# JacdacRgbLed1Ec30_77.net
KiCad netlist of a schematic drawn in Altium Designer
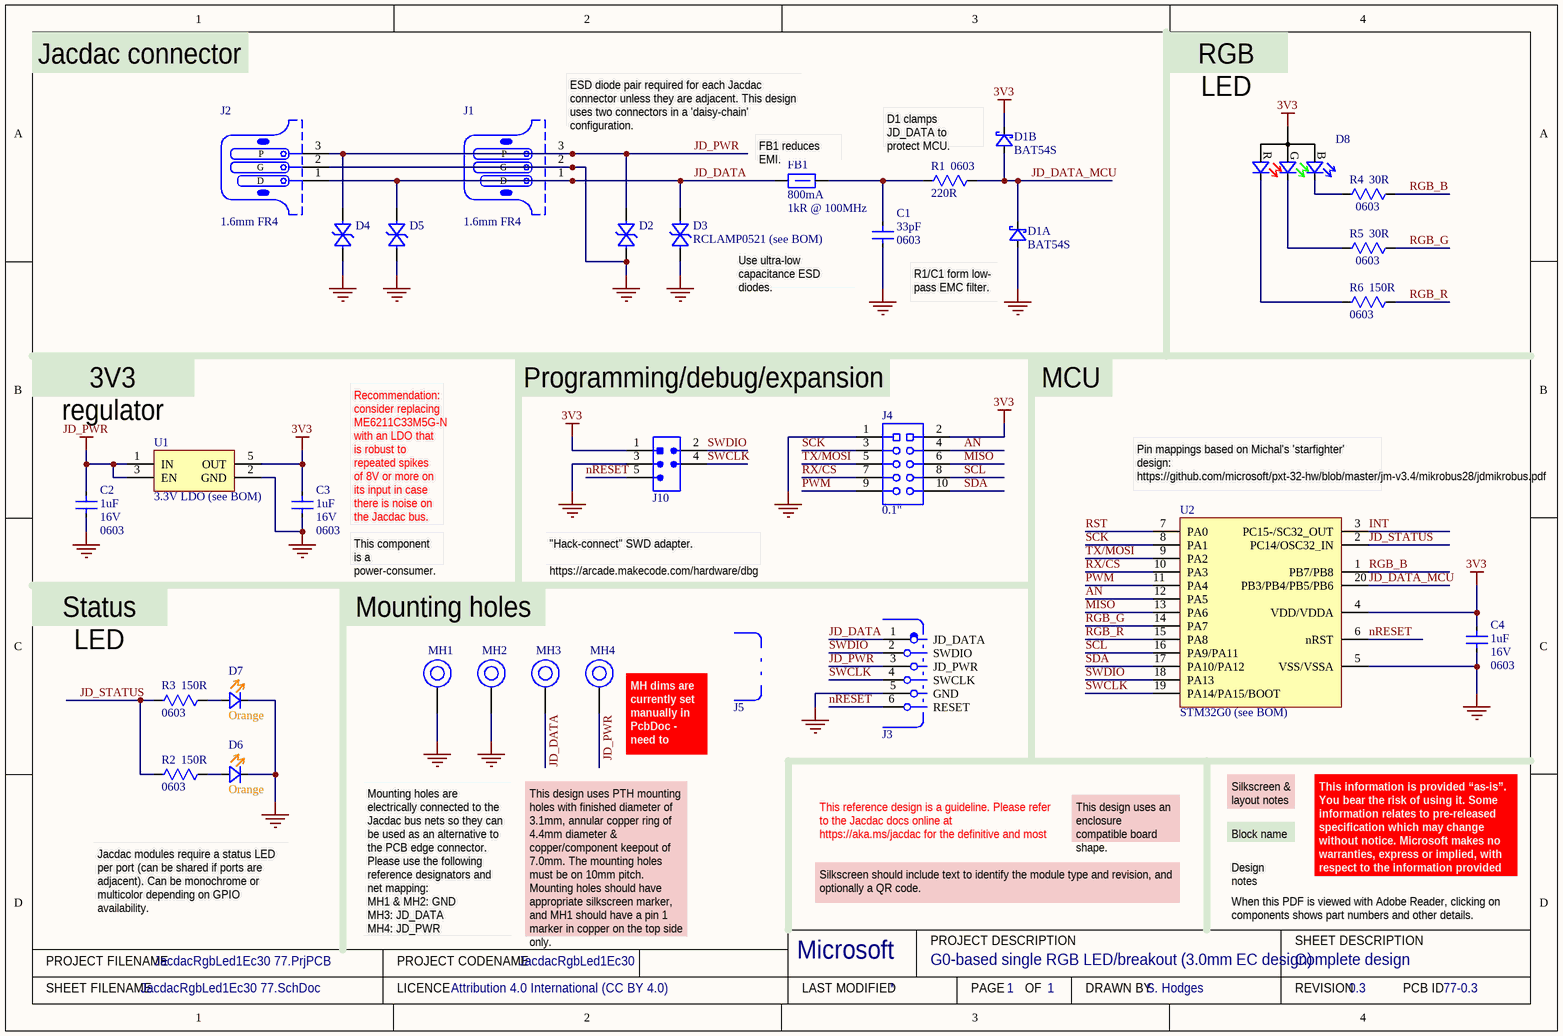
[diagram p0: JacdacRgbLed1Ec30 77.SchDoc]

(export (version "E")
  (design (tool "Eeschema 10.0.6"))
  (components
    (comp (ref "C1")
      (value "33pF")
      (footprint "CC0603")
      (description "Cap 33PF 50V 0603 SMD 5% NP0")
      (fields
        (field (name "VOLTAGE") "50V")
        (field (name "CAPACITANCE") "33pF")
        (field (name "TOLERANCE") "5%")
        (field (name "CASE/PACKAGE") "0603")
      )
      (libsource (lib "Yageo") (part "CC0603JRNPO9BN330"))
    )
    (comp (ref "C2")
      (value "1uF 16V")
      (footprint "SAMSUNG-CAP-0603:C0603 - without outline")
      (description "SMD Multilayer Ceramic Capacitor, 1 µF, 16 V, 0603 [1608 Metric], ± 10%, X5R, CL Series")
      (fields
        (field (name "TOLERANCE") "10%")
        (field (name "VOLTAGE") "16V")
        (field (name "CASE/PACKAGE") "0603")
        (field (name "CAPACITANCE") "1uF")
      )
      (libsource (lib "Samsung") (part "CL10A105KO8NNNC"))
    )
    (comp (ref "C3")
      (value "1uF 16V")
      (footprint "SAMSUNG-CAP-0603:C0603 - without outline")
      (description "SMD Multilayer Ceramic Capacitor, 1 µF, 16 V, 0603 [1608 Metric], ± 10%, X5R, CL Series")
      (fields
        (field (name "TOLERANCE") "10%")
        (field (name "VOLTAGE") "16V")
        (field (name "CASE/PACKAGE") "0603")
        (field (name "CAPACITANCE") "1uF")
      )
      (libsource (lib "Samsung") (part "CL10A105KO8NNNC"))
    )
    (comp (ref "C4")
      (value "1uF 16V")
      (footprint "SAMSUNG-CAP-0603:C0603 - without outline")
      (description "SMD Multilayer Ceramic Capacitor, 1 µF, 16 V, 0603 [1608 Metric], ± 10%, X5R, CL Series")
      (fields
        (field (name "TOLERANCE") "10%")
        (field (name "VOLTAGE") "16V")
        (field (name "CASE/PACKAGE") "0603")
        (field (name "CAPACITANCE") "1uF")
      )
      (libsource (lib "Samsung") (part "CL10A105KO8NNNC"))
    )
    (comp (ref "D1")
      (value "BAT54S")
      (footprint "NXP-BAT54S-TO-236AB - without outline")
      (description "DIODE ARRAY SCHOTTKY 30V SOT23")
      (fields (field (name "MANUFACTURER") "Nexperia") (field (name "MANUFACTURER PART NUMBER") "BAT54S"))
      (libsource (lib "NXP") (part "BAT54S"))
    )
    (comp (ref "D2")
      (value "RCLAMP0521P-N")
      (footprint "TVS 0402 - L")
      (description "Bidirectional 5V (Max) 6V 16V 3.5A (8/20us) 0402 TVS RoHS")
      (fields (field (name "CREATED BY") "D Gakure") (field (name "CHECKED BY") "?"))
      (libsource (lib "BornSemiconductor") (part "RCLAMP0521P-N"))
    )
    (comp (ref "D3")
      (value "RCLAMP0521P-N")
      (footprint "TVS 0402 - L")
      (description "Bidirectional 5V (Max) 6V 16V 3.5A (8/20us) 0402 TVS RoHS")
      (fields
        (field (name "MANUFACTURER PART NUMBER 1") "RCLAMP0521 (see BOM)")
        (field (name "CREATED BY") "D Gakure")
        (field (name "CHECKED BY") "?")
      )
      (libsource (lib "BornSemiconductor") (part "RCLAMP0521P-N"))
    )
    (comp (ref "D4")
      (value "RCLAMP0521P-N")
      (footprint "TVS 0402 - L")
      (description "Bidirectional 5V (Max) 6V 16V 3.5A (8/20us) 0402 TVS RoHS")
      (fields (field (name "CREATED BY") "D Gakure") (field (name "CHECKED BY") "?"))
      (libsource (lib "BornSemiconductor") (part "RCLAMP0521P-N"))
    )
    (comp (ref "D5")
      (value "RCLAMP0521P-N")
      (footprint "TVS 0402 - L")
      (description "Bidirectional 5V (Max) 6V 16V 3.5A (8/20us) 0402 TVS RoHS")
      (fields (field (name "CREATED BY") "D Gakure") (field (name "CHECKED BY") "?"))
      (libsource (lib "BornSemiconductor") (part "RCLAMP0521P-N"))
    )
    (comp (ref "D6")
      (value "~")
      (footprint "0603 Orange")
      (description "LED ORANGE DIFFUSED 0603 SMD")
      (fields (field (name "COLOUR") "Orange"))
      (libsource (lib "EverlightElec") (part "19-217/S2C-AQ1R1B/3T"))
    )
    (comp (ref "D7")
      (value "~")
      (footprint "0603 Orange")
      (description "LED ORANGE DIFFUSED 0603 SMD")
      (fields (field (name "COLOUR") "Orange"))
      (libsource (lib "EverlightElec") (part "19-217/S2C-AQ1R1B/3T"))
    )
    (comp (ref "D8")
      (value "TZ-P4-1615RGBTCA1-0.55T")
      (footprint "TZ-P4-1615RGBTCA1-0.55T")
      (description "1615 Light Emitting Diodes (LED) RoHS")
      (fields (field (name "CREATED BY") "D. Gakure") (field (name "CHECKED BY") "?"))
      (libsource (lib "Tuozhan") (part "TZ-P4-1615RGBTCA1-0.55T"))
    )
    (comp (ref "FB1")
      (value "TDK MPZ1608S102ATA00")
      (footprint "TDK MPZ1608 0.8mm - without outline")
      (description "0603 1k@100MHz 0.8A chip")
      (fields
        (field (name "TOLERANCE") "25%")
        (field (name "MANUFACTURER") "TDK")
        (field (name "CURRENT RATING") "800mA")
        (field (name "IMPEDANCE") "1kR @ 100MHz")
      )
      (libsource (lib "TDK") (part "TDK MPZ1608S102ATA00"))
    )
    (comp (ref "J1")
      (value "3 pin JACDAC edge connector")
      (footprint "JACDAC_EDGE_CONNECTOR_NO_TRACES")
      (description "3 pin Jacdac edge connector 1.27mm pitch")
      (fields
        (field (name "MANUFACTURER PART NUMBER") "JACDAC_EDGE_CONNECTOR")
        (field (name "PCB TYPE") "1.6mm FR4")
        (field (name "CHECKED BY") "?")
        (field (name "CREATED BY") "D. Gakure")
      )
      (libsource (lib "generic-con") (part "Jacdac edge connector"))
    )
    (comp (ref "J2")
      (value "3 pin JACDAC edge connector")
      (footprint "JACDAC_edge_connector:JACDAC_EDGE_CONNECTOR_NO_TRACES")
      (description "3 pin Jacdac edge connector 1.27mm pitch")
      (fields
        (field (name "MANUFACTURER PART NUMBER") "JACDAC_EDGE_CONNECTOR")
        (field (name "PCB TYPE") "1.6mm FR4")
        (field (name "CHECKED BY") "?")
        (field (name "CREATED BY") "D. Gakure")
      )
      (libsource (lib "generic-con") (part "Jacdac edge connector"))
    )
    (comp (ref "J3")
      (value "3x2 way 'mouse bite' connector for Jacdac and SWD")
      (footprint "MiscConnectors:MOUSEBITE_CONNECTOR_3x2")
      (libsource (lib "generic-con") (part "MOUSEBITE_CONNECTOR_3x2_JDSWD"))
    )
    (comp (ref "J4")
      (value "0.1\"")
      (footprint "generic-con-0.1inch:Generic 2x5 2.54mm header")
      (description "2.54mm, 5x2 way, vertical, square pin, gold plate")
      (fields (field (name "MANUFACTURER") "Multicomp") (field (name "MANUFACTURER PART NUMBER") "2213S-10G"))
      (libsource (lib "generic-con") (part "Header Multicomp 2213S-10G-whitesch"))
    )
    (comp (ref "J5")
      (value "3 way 'mouse bite' connector")
      (footprint "MiscConnectors:MOUSEBITE_NOCONNECTOR_3")
      (libsource (lib "generic-con") (part "MOUSEBITE_NOCONNECTOR_3"))
    )
    (comp (ref "J10")
      (value "Hack Connect Mini 1.27 mm pitch 2-row")
      (footprint "HACK_CONNECT_MINI_5_X_1_27")
      (libsource (lib "HackConnect") (part "HACK_CONNECT_MINI"))
    )
    (comp (ref "MH1")
      (value "MH_6.5MMK_4.5MMC_3.0MMD_PTH")
      (footprint "MH_6.5MMK_4.5MMC_3.0MMD_PTH")
      (description "Mounting Hole 6.5mm keepout, 4.5mm annualar ring and 3.0mm Drill PTH")
      (libsource (lib "generic") (part "MH_6.5MMK_4.5MMC_3.0MMD_PTH"))
    )
    (comp (ref "MH2")
      (value "MH_6.5MMK_4.5MMC_3.0MMD_PTH")
      (footprint "MH_6.5MMK_4.5MMC_3.0MMD_PTH")
      (description "Mounting Hole 6.5mm keepout, 4.5mm annualar ring and 3.0mm Drill PTH")
      (libsource (lib "generic") (part "MH_6.5MMK_4.5MMC_3.0MMD_PTH"))
    )
    (comp (ref "MH3")
      (value "MH_6.5MMK_4.5MMC_3.0MMD_PTH")
      (footprint "MH_6.5MMK_4.5MMC_3.0MMD_PTH")
      (description "Mounting Hole 6.5mm keepout, 4.5mm annualar ring and 3.0mm Drill PTH")
      (libsource (lib "generic") (part "MH_6.5MMK_4.5MMC_3.0MMD_PTH"))
    )
    (comp (ref "MH4")
      (value "MH_6.5MMK_4.5MMC_3.0MMD_PTH")
      (footprint "MH_6.5MMK_4.5MMC_3.0MMD_PTH")
      (description "Mounting Hole 6.5mm keepout, 4.5mm annualar ring and 3.0mm Drill PTH")
      (libsource (lib "generic") (part "MH_6.5MMK_4.5MMC_3.0MMD_PTH"))
    )
    (comp (ref "R1")
      (value "220R")
      (footprint "YAGEO-0603:RC0603")
      (description "Res Thick Film 0603 220 Ohm 1% 0.1W(1/10W) ±100ppm/°C Pad SMD T/R")
      (fields
        (field (name "TOLERANCE") "1%")
        (field (name "RESISTANCE") "220R")
        (field (name "CASE/PACKAGE") "0603")
      )
      (libsource (lib "Yageo") (part "RC0603FR-07220RL"))
    )
    (comp (ref "R2")
      (value "150R")
      (footprint "YAGEO-0603:RC0603")
      (description "Res General Purpose Thick Film 0603 150 Ohm 1% 1/10W ±100ppm/°C Molded SMD Paper T/R")
      (fields
        (field (name "TOLERANCE") "1%")
        (field (name "CASE/PACKAGE") "0603")
        (field (name "RESISTANCE") "150R")
      )
      (libsource (lib "Yageo") (part "RC0603FR-07150RL"))
    )
    (comp (ref "R3")
      (value "150R")
      (footprint "YAGEO-0603:RC0603")
      (description "Res General Purpose Thick Film 0603 150 Ohm 1% 1/10W ±100ppm/°C Molded SMD Paper T/R")
      (fields
        (field (name "TOLERANCE") "1%")
        (field (name "CASE/PACKAGE") "0603")
        (field (name "RESISTANCE") "150R")
      )
      (libsource (lib "Yageo") (part "RC0603FR-07150RL"))
    )
    (comp (ref "R4")
      (value "30R")
      (footprint "YAGEO-0603:RC0603")
      (description "Res Thick Film 0603 30 Ohm 1% 0.1W(1/10W) ±100ppm/C Pad SMD T/R")
      (fields
        (field (name "TOLERANCE") "1%")
        (field (name "RESISTANCE") "30R")
        (field (name "CASE/PACKAGE") "0603")
      )
      (libsource (lib "Yageo") (part "RC0603FR-0730RL"))
    )
    (comp (ref "R5")
      (value "30R")
      (footprint "YAGEO-0603:RC0603")
      (description "Res Thick Film 0603 30 Ohm 1% 0.1W(1/10W) ±100ppm/C Pad SMD T/R")
      (fields
        (field (name "TOLERANCE") "1%")
        (field (name "RESISTANCE") "30R")
        (field (name "CASE/PACKAGE") "0603")
      )
      (libsource (lib "Yageo") (part "RC0603FR-0730RL"))
    )
    (comp (ref "R6")
      (value "150R")
      (footprint "YAGEO-0603:RC0603")
      (description "Res General Purpose Thick Film 0603 150 Ohm 1% 1/10W ±100ppm/°C Molded SMD Paper T/R")
      (fields
        (field (name "TOLERANCE") "1%")
        (field (name "CASE/PACKAGE") "0603")
        (field (name "RESISTANCE") "150R")
      )
      (libsource (lib "Yageo") (part "RC0603FR-07150RL"))
    )
    (comp (ref "U1")
      (value "~")
      (footprint "MICRONE-SOT23-5")
      (description "6V 260mV @ 200mA(typ) - - Fixed 3.3V SOT-23-5 Linear Voltage Regulators (LDO) ROHS")
      (fields
        (field (name "MANUFACTURER PART NUMBER 1") "3.3V LDO (see BOM)")
        (field (name "CREATED") "DG")
        (field (name "CHECKED") "?")
      )
      (libsource (lib "MICRONE(NanjingMicroOneElec)") (part "ME6211C33M5G-N"))
    )
    (comp (ref "U2")
      (value "STM32G0 (see BOM)")
      (footprint "20-TSSOP")
      (description "MCU 32-Bit STM32G031 ARM Cortex-M0+ RISC 32KB Flash 1.7V to 3.6V 20-Pin TSSOP Tube")
      (fields
        (field (name "MANUFACTURER") "STMicroelectronics")
        (field (name "MANUFACTURER PART NUMBER") "STM32G0 (see BOM)")
        (field (name "CREATED BY") "D. Gakure")
        (field (name "CHECKED BY") "?")
      )
      (libsource (lib "ST") (part "STM32G031F6P6"))
    )
  )
  (nets
    (net (code "1") (name "/AN") (class "Default")
      (node (ref "J4") (pin "4") (pinfunction "4_4") (pintype "passive"))
      (node (ref "U2") (pin "12") (pinfunction "PA5_12") (pintype "passive"))
    )
    (net (code "2") (name "/INT") (class "Default")
      (node (ref "U2") (pin "3") (pinfunction "PC15-/SC32_OUT_3") (pintype "passive"))
    )
    (net (code "3") (name "/JD_DATA") (class "Default")
      (node (ref "D3") (pin "1") (pinfunction "K_1") (pintype "passive"))
      (node (ref "D5") (pin "1") (pinfunction "K_1") (pintype "passive"))
      (node (ref "FB1") (pin "1") (pinfunction "1_1") (pintype "passive"))
      (node (ref "J1") (pin "1") (pinfunction "D_1") (pintype "passive"))
      (node (ref "J2") (pin "1") (pinfunction "D_1") (pintype "passive"))
      (node (ref "J3") (pin "1") (pinfunction "JD_DATA_1") (pintype "passive"))
      (node (ref "MH3") (pin "1") (pinfunction "1_1") (pintype "passive"))
    )
    (net (code "4") (name "/JD_DATA_MCU") (class "Default")
      (node (ref "D1") (pin "3") (pinfunction "K_3") (pintype "passive"))
      (node (ref "R1") (pin "2") (pinfunction "2_2") (pintype "passive"))
      (node (ref "U2") (pin "20") (pinfunction "PB3/PB4/PB5/PB6_20") (pintype "power_in"))
    )
    (net (code "5") (name "/JD_STATUS") (class "Default")
      (node (ref "R2") (pin "1") (pinfunction "1_1") (pintype "passive"))
      (node (ref "R3") (pin "1") (pinfunction "1_1") (pintype "passive"))
      (node (ref "U2") (pin "2") (pinfunction "PC14/OSC32_IN_2") (pintype "passive"))
    )
    (net (code "6") (name "/MISO") (class "Default")
      (node (ref "J4") (pin "6") (pinfunction "6_6") (pintype "passive"))
      (node (ref "U2") (pin "13") (pinfunction "PA6_13") (pintype "passive"))
    )
    (net (code "7") (name "/PWM") (class "Default")
      (node (ref "J4") (pin "9") (pinfunction "9_9") (pintype "passive"))
      (node (ref "U2") (pin "11") (pinfunction "PA4_11") (pintype "passive"))
    )
    (net (code "8") (name "/RGB_B") (class "Default")
      (node (ref "R4") (pin "2") (pinfunction "2_2") (pintype "passive"))
      (node (ref "U2") (pin "1") (pinfunction "PB7/PB8_1") (pintype "passive"))
    )
    (net (code "9") (name "/RGB_G") (class "Default")
      (node (ref "R5") (pin "2") (pinfunction "2_2") (pintype "passive"))
      (node (ref "U2") (pin "14") (pinfunction "PA7_14") (pintype "passive"))
    )
    (net (code "10") (name "/RGB_R") (class "Default")
      (node (ref "R6") (pin "2") (pinfunction "2_2") (pintype "passive"))
      (node (ref "U2") (pin "15") (pinfunction "PA8_15") (pintype "passive"))
    )
    (net (code "11") (name "/RST") (class "Default")
      (node (ref "U2") (pin "7") (pinfunction "PA0_7") (pintype "passive"))
    )
    (net (code "12") (name "/RX{slash}CS") (class "Default")
      (node (ref "J4") (pin "7") (pinfunction "7_7") (pintype "passive"))
      (node (ref "U2") (pin "10") (pinfunction "PA3_10") (pintype "passive"))
    )
    (net (code "13") (name "/SCK") (class "Default")
      (node (ref "J4") (pin "3") (pinfunction "3_3") (pintype "passive"))
      (node (ref "U2") (pin "8") (pinfunction "PA1_8") (pintype "passive"))
    )
    (net (code "14") (name "/SCL") (class "Default")
      (node (ref "J4") (pin "8") (pinfunction "8_8") (pintype "passive"))
      (node (ref "U2") (pin "16") (pinfunction "PA9/PA11_16") (pintype "passive"))
    )
    (net (code "15") (name "/SDA") (class "Default")
      (node (ref "J4") (pin "10") (pinfunction "10_10") (pintype "passive"))
      (node (ref "U2") (pin "17") (pinfunction "PA10/PA12_17") (pintype "passive"))
    )
    (net (code "16") (name "/SWCLK") (class "Default")
      (node (ref "J10") (pin "4") (pinfunction "SWCLK_4") (pintype "passive"))
      (node (ref "J3") (pin "4") (pinfunction "SWCLK_4") (pintype "passive"))
      (node (ref "U2") (pin "19") (pinfunction "PA14/PA15/BOOT_19") (pintype "passive"))
    )
    (net (code "17") (name "/SWDIO") (class "Default")
      (node (ref "J10") (pin "2") (pinfunction "SWDIO_2") (pintype "passive"))
      (node (ref "J3") (pin "2") (pinfunction "SWDIO_2") (pintype "passive"))
      (node (ref "U2") (pin "18") (pinfunction "PA13_18") (pintype "passive"))
    )
    (net (code "18") (name "/TX{slash}MOSI") (class "Default")
      (node (ref "J4") (pin "5") (pinfunction "5_5") (pintype "passive"))
      (node (ref "U2") (pin "9") (pinfunction "PA2_9") (pintype "passive"))
    )
    (net (code "19") (name "/nRESET") (class "Default")
      (node (ref "J10") (pin "5") (pinfunction "RESET_5") (pintype "passive"))
      (node (ref "J3") (pin "6") (pinfunction "RESET_6") (pintype "passive"))
      (node (ref "U2") (pin "6") (pinfunction "nRST_6") (pintype "power_in"))
    )
    (net (code "20") (name "3V3") (class "Default")
      (node (ref "C3") (pin "2") (pinfunction "2_2") (pintype "passive"))
      (node (ref "C4") (pin "2") (pinfunction "2_2") (pintype "passive"))
      (node (ref "D1") (pin "2") (pinfunction "K_2") (pintype "passive"))
      (node (ref "D8") (pin "1") (pinfunction "A_1") (pintype "passive"))
      (node (ref "J10") (pin "1") (pinfunction "VCC_1") (pintype "passive"))
      (node (ref "J4") (pin "2") (pinfunction "2_2") (pintype "passive"))
      (node (ref "U1") (pin "5") (pinfunction "OUT_5") (pintype "passive"))
      (node (ref "U2") (pin "4") (pinfunction "VDD/VDDA_4") (pintype "passive"))
    )
    (net (code "21") (name "GND") (class "Default")
      (node (ref "C1") (pin "1") (pinfunction "1_1") (pintype "passive"))
      (node (ref "C2") (pin "1") (pinfunction "1_1") (pintype "passive"))
      (node (ref "C3") (pin "1") (pinfunction "1_1") (pintype "passive"))
      (node (ref "C4") (pin "1") (pinfunction "1_1") (pintype "passive"))
      (node (ref "D1") (pin "1") (pinfunction "A_1") (pintype "passive"))
      (node (ref "D2") (pin "2") (pinfunction "A_2") (pintype "passive"))
      (node (ref "D3") (pin "2") (pinfunction "A_2") (pintype "passive"))
      (node (ref "D4") (pin "2") (pinfunction "A_2") (pintype "passive"))
      (node (ref "D5") (pin "2") (pinfunction "A_2") (pintype "passive"))
      (node (ref "D6") (pin "1") (pinfunction "K_1") (pintype "passive"))
      (node (ref "D7") (pin "1") (pinfunction "K_1") (pintype "passive"))
      (node (ref "J1") (pin "2") (pinfunction "G_2") (pintype "passive"))
      (node (ref "J10") (pin "3") (pinfunction "GND_3") (pintype "passive"))
      (node (ref "J2") (pin "2") (pinfunction "G_2") (pintype "passive"))
      (node (ref "J3") (pin "5") (pinfunction "GND_5") (pintype "passive"))
      (node (ref "J4") (pin "1") (pinfunction "1_1") (pintype "passive"))
      (node (ref "MH1") (pin "1") (pinfunction "1_1") (pintype "passive"))
      (node (ref "MH2") (pin "1") (pinfunction "1_1") (pintype "passive"))
      (node (ref "U1") (pin "2") (pinfunction "GND_2") (pintype "passive"))
      (node (ref "U2") (pin "5") (pinfunction "VSS/VSSA_5") (pintype "power_in"))
    )
    (net (code "22") (name "JD_PWR") (class "Default")
      (node (ref "C2") (pin "2") (pinfunction "2_2") (pintype "passive"))
      (node (ref "D2") (pin "1") (pinfunction "K_1") (pintype "passive"))
      (node (ref "D4") (pin "1") (pinfunction "K_1") (pintype "passive"))
      (node (ref "J1") (pin "3") (pinfunction "P_3") (pintype "passive"))
      (node (ref "J2") (pin "3") (pinfunction "P_3") (pintype "passive"))
      (node (ref "J3") (pin "3") (pinfunction "JD_PWR_3") (pintype "passive"))
      (node (ref "MH4") (pin "1") (pinfunction "1_1") (pintype "passive"))
      (node (ref "U1") (pin "1") (pinfunction "IN_1") (pintype "passive"))
      (node (ref "U1") (pin "3") (pinfunction "EN_3") (pintype "passive"))
    )
    (net (code "23") (name "Net-(C1-Pad2)") (class "Default")
      (node (ref "C1") (pin "2") (pinfunction "2_2") (pintype "passive"))
      (node (ref "FB1") (pin "2") (pinfunction "2_2") (pintype "passive"))
      (node (ref "R1") (pin "1") (pinfunction "1_1") (pintype "passive"))
    )
    (net (code "24") (name "Net-(D6-A)") (class "Default")
      (node (ref "D6") (pin "2") (pinfunction "A_2") (pintype "passive"))
      (node (ref "R2") (pin "2") (pinfunction "2_2") (pintype "passive"))
    )
    (net (code "25") (name "Net-(D7-A)") (class "Default")
      (node (ref "D7") (pin "2") (pinfunction "A_2") (pintype "passive"))
      (node (ref "R3") (pin "2") (pinfunction "2_2") (pintype "passive"))
    )
    (net (code "26") (name "Net-(D8-B)") (class "Default")
      (node (ref "D8") (pin "4") (pinfunction "B_4") (pintype "passive"))
      (node (ref "R4") (pin "1") (pinfunction "1_1") (pintype "passive"))
    )
    (net (code "27") (name "Net-(D8-G)") (class "Default")
      (node (ref "D8") (pin "3") (pinfunction "G_3") (pintype "passive"))
      (node (ref "R5") (pin "1") (pinfunction "1_1") (pintype "passive"))
    )
    (net (code "28") (name "Net-(D8-R)") (class "Default")
      (node (ref "D8") (pin "2") (pinfunction "R_2") (pintype "passive"))
      (node (ref "R6") (pin "1") (pinfunction "1_1") (pintype "passive"))
    )
  )
)
